# Power.net
KiCad netlist of a schematic drawn in Altium Designer
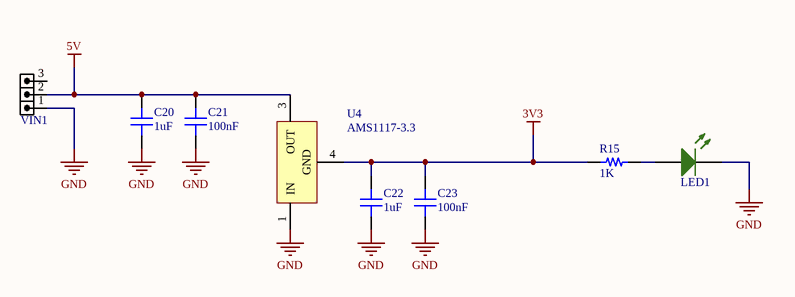
[diagram p0: Power.SchDoc]

(export (version "E")
  (design (tool "Eeschema 10.0.6"))
  (components
    (comp (ref "C20")
      (value "1uF")
      (footprint "CAP 0805_2012")
      (description "SMT Capacitor")
      (libsource (lib "Capacitor") (part "Cap 0805"))
    )
    (comp (ref "C21")
      (value "100nF")
      (footprint "CAP 0603_1608")
      (description "SMT Capacitor")
      (libsource (lib "Capacitor") (part "Cap 0603"))
    )
    (comp (ref "C22")
      (value "1uF")
      (footprint "CAP 0805_2012")
      (description "SMT Capacitor")
      (libsource (lib "Capacitor") (part "Cap 0805"))
    )
    (comp (ref "C23")
      (value "100nF")
      (footprint "CAP 0603_1608")
      (description "SMT Capacitor")
      (libsource (lib "Capacitor") (part "Cap 0603"))
    )
    (comp (ref "LED1")
      (value "LED SMD 0603 GREEN")
      (footprint "LED_0603_GREEN")
      (libsource (lib "Led") (part "LED SMD 0603 GREEN"))
    )
    (comp (ref "R15")
      (value "1K")
      (footprint "RES 0603_1608")
      (description "SMT Resistor")
      (libsource (lib "Resistor") (part "Res 0603"))
    )
    (comp (ref "U4")
      (value "AMS1117-3.3")
      (footprint "TO-252")
      (fields (field (name "PARTNUMBER") "LF33CDT-TR"))
      (libsource (lib "Chip") (part "LF33 (SMD)"))
    )
    (comp (ref "VIN1")
      (value "HDRM3")
      (footprint "HDR_M_1X3")
      (description "CONN, HEADER, Male, pitch: 2.54mm, 3POS")
      (libsource (lib "Conn Header") (part "HDR_M_1X3"))
    )
  )
  (nets
    (net (code "1") (name "3V3") (class "Default")
      (node (ref "C22") (pin "2") (pinfunction "2_2") (pintype "passive"))
      (node (ref "C23") (pin "2") (pinfunction "2_2") (pintype "passive"))
      (node (ref "R15") (pin "1") (pinfunction "1_1") (pintype "passive"))
      (node (ref "U4") (pin "4") (pinfunction "GND_4") (pintype "power_in"))
    )
    (net (code "2") (name "5V") (class "Default")
      (node (ref "C20") (pin "2") (pinfunction "2_2") (pintype "passive"))
      (node (ref "C21") (pin "2") (pinfunction "2_2") (pintype "passive"))
      (node (ref "U4") (pin "3") (pinfunction "OUT_3") (pintype "power_in"))
      (node (ref "VIN1") (pin "2") (pinfunction "2_2") (pintype "passive"))
    )
    (net (code "3") (name "GND") (class "Default")
      (node (ref "C20") (pin "1") (pinfunction "1_1") (pintype "passive"))
      (node (ref "C21") (pin "1") (pinfunction "1_1") (pintype "passive"))
      (node (ref "C22") (pin "1") (pinfunction "1_1") (pintype "passive"))
      (node (ref "C23") (pin "1") (pinfunction "1_1") (pintype "passive"))
      (node (ref "LED1") (pin "2") (pinfunction "K_2") (pintype "passive"))
      (node (ref "U4") (pin "1") (pinfunction "IN_1") (pintype "power_in"))
      (node (ref "VIN1") (pin "1") (pinfunction "1_1") (pintype "passive"))
    )
    (net (code "4") (name "Net-(LED1-A)") (class "Default")
      (node (ref "LED1") (pin "1") (pinfunction "A_1") (pintype "passive"))
      (node (ref "R15") (pin "2") (pinfunction "2_2") (pintype "passive"))
    )
    (net (code "5") (name "unconnected-(VIN1-Pad3)") (class "Default")
      (node (ref "VIN1") (pin "3") (pinfunction "3_3") (pintype "passive"))
    )
  )
)
